# RC_BD_v2_1.net
KiCad netlist of a schematic drawn in EAGLE
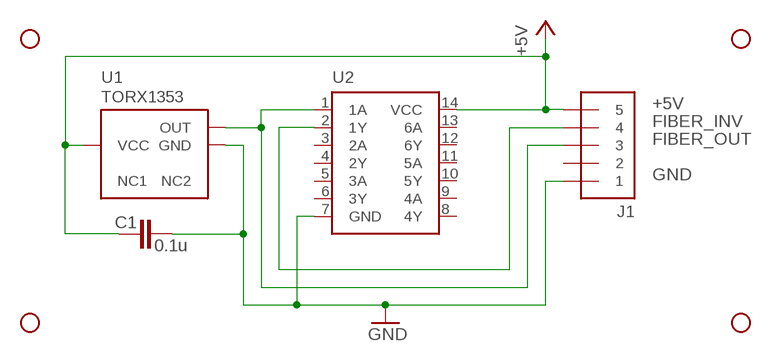
[diagram p0: schematic, sheet 1]

(export (version "E")
  (design (tool "Eeschema 10.0.6"))
  (components
    (comp (ref "C1")
      (value "0.1u")
      (footprint "eagle-import:CAPC3216X135")
      (libsource (lib "eagle-import") (part "CCHIP-1206(3216-METRIC)_"))
    )
    (comp (ref "H1")
      (value "STAND-OFF")
      (footprint "eagle-import:STAND-OFF")
      (libsource (lib "eagle-import") (part "STAND-OFF"))
    )
    (comp (ref "H2")
      (value "STAND-OFF")
      (footprint "eagle-import:STAND-OFF")
      (libsource (lib "eagle-import") (part "STAND-OFF"))
    )
    (comp (ref "H3")
      (value "STAND-OFF")
      (footprint "eagle-import:STAND-OFF")
      (libsource (lib "eagle-import") (part "STAND-OFF"))
    )
    (comp (ref "H4")
      (value "STAND-OFF")
      (footprint "eagle-import:STAND-OFF")
      (libsource (lib "eagle-import") (part "STAND-OFF"))
    )
    (comp (ref "J1")
      (value "PPTC051LFBN-RC")
      (footprint "eagle-import:HDR-5-F")
      (libsource (lib "eagle-import") (part "PPTC051LFBN-RC"))
    )
    (comp (ref "U1")
      (value "TORX1353")
      (footprint "eagle-import:TOXX1353")
      (libsource (lib "eagle-import") (part "TORX1353"))
    )
    (comp (ref "U2")
      (value "SN74HC04AN")
      (footprint "eagle-import:DIL14")
      (libsource (lib "eagle-import") (part "SN74HC04AN"))
    )
  )
  (nets
    (net (code "1") (name "+5V") (class "Default")
      (node (ref "C1") (pin "1") (pinfunction "1_1") (pintype "passive"))
      (node (ref "J1") (pin "5") (pinfunction "5_5") (pintype "bidirectional"))
      (node (ref "U1") (pin "3") (pinfunction "VCC_3") (pintype "power_in"))
      (node (ref "U2") (pin "14") (pinfunction "VCC_14") (pintype "power_in"))
    )
    (net (code "2") (name "/FIBER_INV") (class "Default")
      (node (ref "J1") (pin "4") (pinfunction "4_4") (pintype "bidirectional"))
      (node (ref "U2") (pin "2") (pinfunction "1Y_2") (pintype "output"))
    )
    (net (code "3") (name "/FIBER_OUT") (class "Default")
      (node (ref "J1") (pin "3") (pinfunction "3_3") (pintype "bidirectional"))
      (node (ref "U1") (pin "1") (pinfunction "OUT_1") (pintype "output"))
      (node (ref "U2") (pin "1") (pinfunction "1A_1") (pintype "input"))
    )
    (net (code "4") (name "GND") (class "Default")
      (node (ref "C1") (pin "2") (pinfunction "2_2") (pintype "passive"))
      (node (ref "J1") (pin "1") (pinfunction "1_1") (pintype "bidirectional"))
      (node (ref "U1") (pin "2") (pinfunction "GND_2") (pintype "power_in"))
      (node (ref "U2") (pin "7") (pinfunction "GND_7") (pintype "power_in"))
    )
    (net (code "5") (name "unconnected-(J1-Pad2)") (class "Default")
      (node (ref "J1") (pin "2") (pinfunction "2_2") (pintype "bidirectional"))
    )
    (net (code "6") (name "unconnected-(U1-NC1-Pad4)") (class "Default")
      (node (ref "U1") (pin "4") (pinfunction "NC1_4") (pintype "no_connect"))
    )
    (net (code "7") (name "unconnected-(U1-NC2-Pad5)") (class "Default")
      (node (ref "U1") (pin "5") (pinfunction "NC2_5") (pintype "no_connect"))
    )
    (net (code "8") (name "unconnected-(U2-2A-Pad3)") (class "Default")
      (node (ref "U2") (pin "3") (pinfunction "2A_3") (pintype "input"))
    )
    (net (code "9") (name "unconnected-(U2-2Y-Pad4)") (class "Default")
      (node (ref "U2") (pin "4") (pinfunction "2Y_4") (pintype "output"))
    )
    (net (code "10") (name "unconnected-(U2-3A-Pad5)") (class "Default")
      (node (ref "U2") (pin "5") (pinfunction "3A_5") (pintype "input"))
    )
    (net (code "11") (name "unconnected-(U2-3Y-Pad6)") (class "Default")
      (node (ref "U2") (pin "6") (pinfunction "3Y_6") (pintype "output"))
    )
    (net (code "12") (name "unconnected-(U2-4A-Pad9)") (class "Default")
      (node (ref "U2") (pin "9") (pinfunction "4A_9") (pintype "input"))
    )
    (net (code "13") (name "unconnected-(U2-4Y-Pad8)") (class "Default")
      (node (ref "U2") (pin "8") (pinfunction "4Y_8") (pintype "output"))
    )
    (net (code "14") (name "unconnected-(U2-5A-Pad11)") (class "Default")
      (node (ref "U2") (pin "11") (pinfunction "5A_11") (pintype "input"))
    )
    (net (code "15") (name "unconnected-(U2-5Y-Pad10)") (class "Default")
      (node (ref "U2") (pin "10") (pinfunction "5Y_10") (pintype "output"))
    )
    (net (code "16") (name "unconnected-(U2-6A-Pad13)") (class "Default")
      (node (ref "U2") (pin "13") (pinfunction "6A_13") (pintype "input"))
    )
    (net (code "17") (name "unconnected-(U2-6Y-Pad12)") (class "Default")
      (node (ref "U2") (pin "12") (pinfunction "6Y_12") (pintype "output"))
    )
  )
)
